# PS2.net
KiCad netlist of a schematic drawn in EAGLE
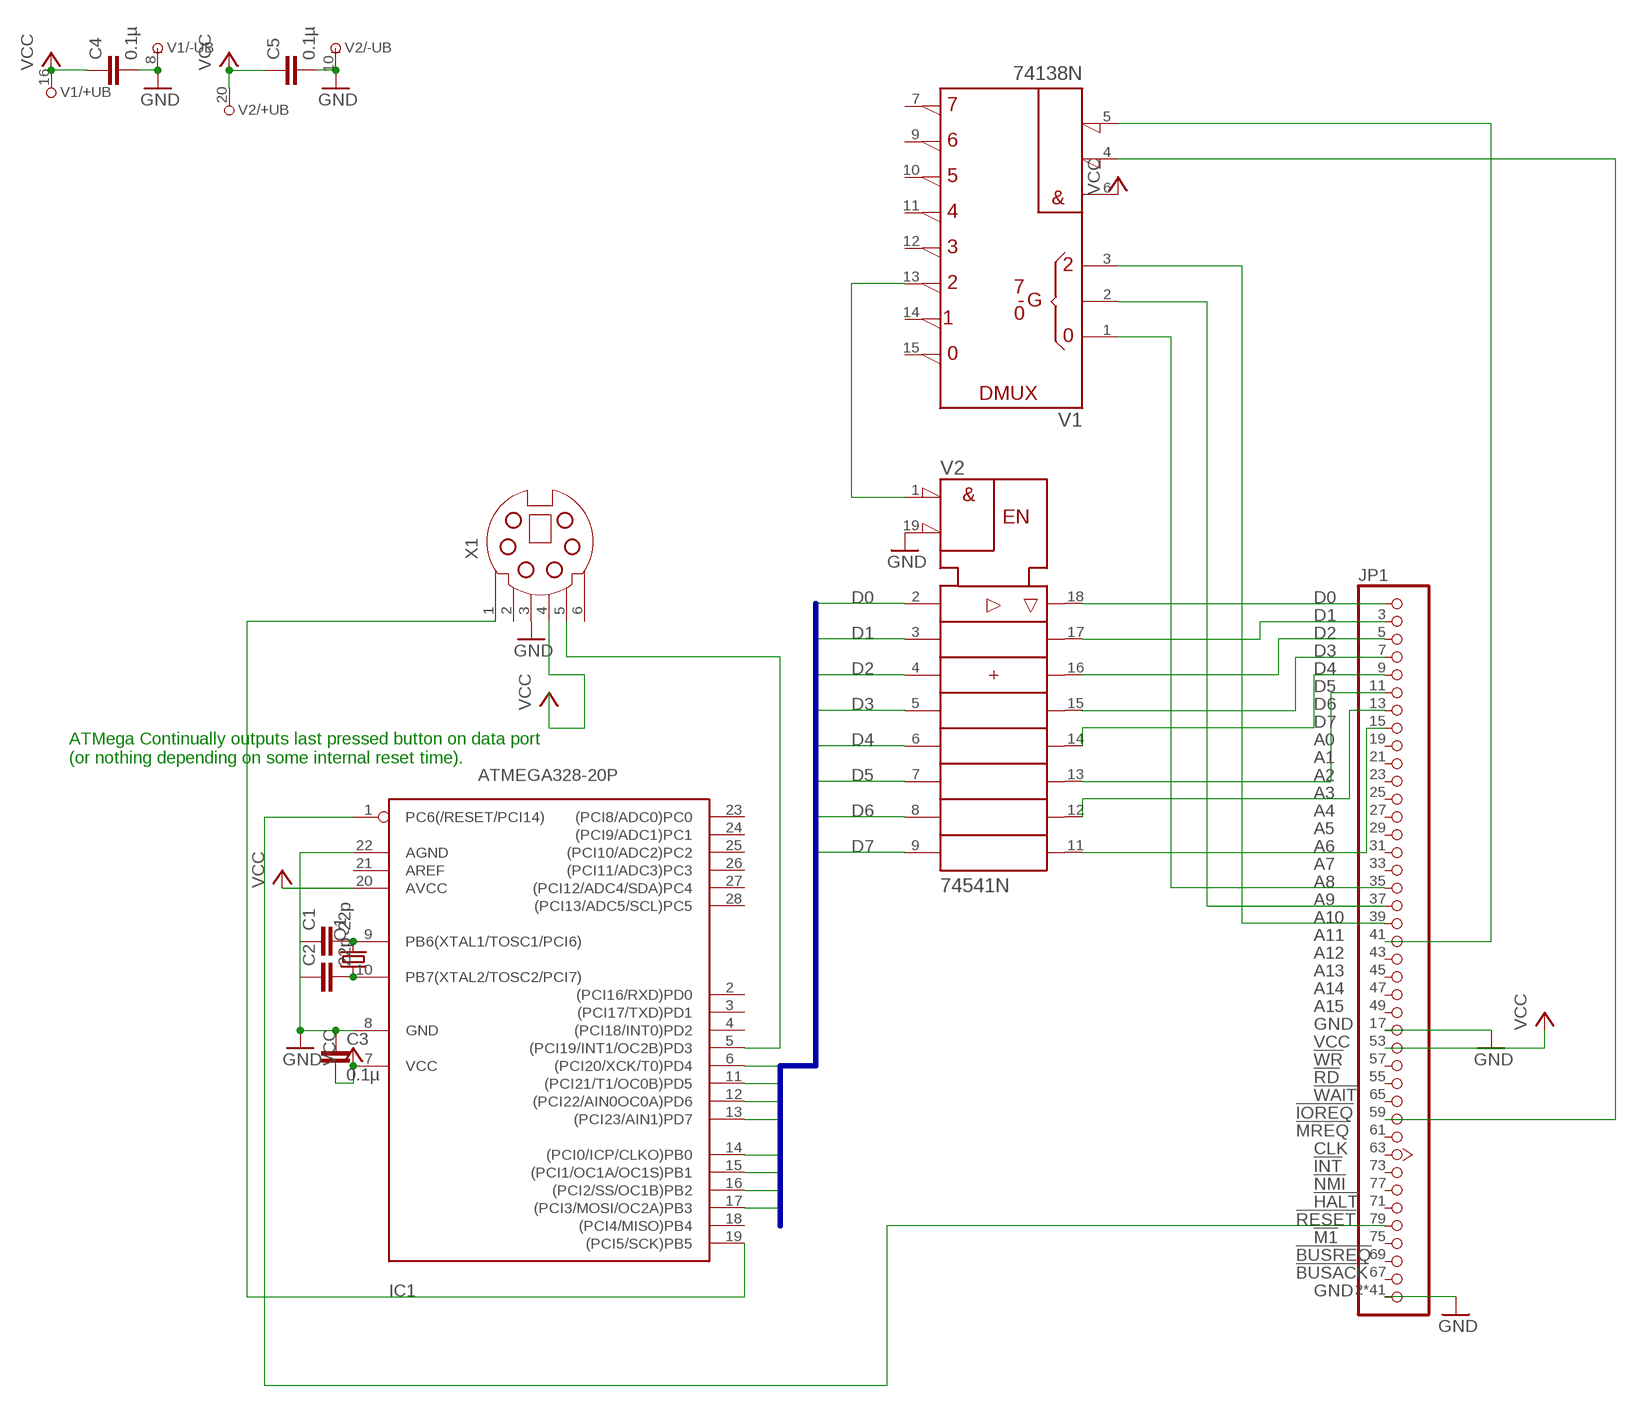
[diagram p0: schematic, sheet 1]

(export (version "E")
  (design (tool "Eeschema 10.0.6"))
  (components
    (comp (ref "C1")
      (value "22p")
      (footprint "eagle-import:C5B3")
      (libsource (lib "eagle-import") (part "C5/3"))
    )
    (comp (ref "C2")
      (value "22p")
      (footprint "eagle-import:C5B3")
      (libsource (lib "eagle-import") (part "C5/3"))
    )
    (comp (ref "C3")
      (value "0.1µ")
      (footprint "eagle-import:C5B3")
      (libsource (lib "eagle-import") (part "C5/3"))
    )
    (comp (ref "C4")
      (value "0.1µ")
      (footprint "eagle-import:C5B3")
      (libsource (lib "eagle-import") (part "C5/3"))
    )
    (comp (ref "C5")
      (value "0.1µ")
      (footprint "eagle-import:C5B3")
      (libsource (lib "eagle-import") (part "C5/3"))
    )
    (comp (ref "IC1")
      (value "ATMEGA328-20P")
      (footprint "eagle-import:DIL28-3")
      (libsource (lib "eagle-import") (part "ATMEGA328P-20"))
    )
    (comp (ref "JP1")
      (value "JEANNECTOR/90")
      (footprint "eagle-import:2X25_90")
      (libsource (lib "eagle-import") (part "JEANNECTOR/90"))
    )
    (comp (ref "Q1")
      (value "CRYSTALHC49S")
      (footprint "eagle-import:HC49_S")
      (libsource (lib "eagle-import") (part "CRYSTALHC49S"))
    )
    (comp (ref "V1")
      (value "74138N")
      (footprint "eagle-import:DIL16")
      (libsource (lib "eagle-import") (part "74138N"))
    )
    (comp (ref "V2")
      (value "74541N")
      (footprint "eagle-import:DIL20")
      (libsource (lib "eagle-import") (part "74541N"))
    )
    (comp (ref "X1")
      (value "MDSSV-F06")
      (footprint "eagle-import:SSV-BC06")
      (libsource (lib "eagle-import") (part "MDSSV-F06"))
    )
  )
  (nets
    (net (code "1") (name "/D0") (class "Default")
      (node (ref "IC1") (pin "6") (pinfunction "(PCI20/XCK/T0)PD4_6") (pintype "bidirectional"))
      (node (ref "V2") (pin "2") (pinfunction "A1_2") (pintype "input"))
    )
    (net (code "2") (name "/D1") (class "Default")
      (node (ref "IC1") (pin "11") (pinfunction "(PCI21/T1/OC0B)PD5_11") (pintype "bidirectional"))
      (node (ref "V2") (pin "3") (pinfunction "A2_3") (pintype "input"))
    )
    (net (code "3") (name "/D2") (class "Default")
      (node (ref "IC1") (pin "12") (pinfunction "(PCI22/AIN0OC0A)PD6_12") (pintype "bidirectional"))
      (node (ref "V2") (pin "4") (pinfunction "A3_4") (pintype "input"))
    )
    (net (code "4") (name "/D3") (class "Default")
      (node (ref "IC1") (pin "13") (pinfunction "(PCI23/AIN1)PD7_13") (pintype "bidirectional"))
      (node (ref "V2") (pin "5") (pinfunction "A4_5") (pintype "input"))
    )
    (net (code "5") (name "/D4") (class "Default")
      (node (ref "IC1") (pin "14") (pinfunction "(PCI0/ICP/CLKO)PB0_14") (pintype "bidirectional"))
      (node (ref "V2") (pin "6") (pinfunction "A5_6") (pintype "input"))
    )
    (net (code "6") (name "/D5") (class "Default")
      (node (ref "IC1") (pin "15") (pinfunction "(PCI1/OC1A/OC1S)PB1_15") (pintype "bidirectional"))
      (node (ref "V2") (pin "7") (pinfunction "A6_7") (pintype "input"))
    )
    (net (code "7") (name "/D6") (class "Default")
      (node (ref "IC1") (pin "16") (pinfunction "(PCI2/SS/OC1B)PB2_16") (pintype "bidirectional"))
      (node (ref "V2") (pin "8") (pinfunction "A7_8") (pintype "input"))
    )
    (net (code "8") (name "/D7") (class "Default")
      (node (ref "IC1") (pin "17") (pinfunction "(PCI3/MOSI/OC2A)PB3_17") (pintype "bidirectional"))
      (node (ref "V2") (pin "9") (pinfunction "A8_9") (pintype "input"))
    )
    (net (code "9") (name "GND") (class "Default")
      (node (ref "C3") (pin "1") (pinfunction "1_1") (pintype "passive"))
      (node (ref "C4") (pin "2") (pinfunction "2_2") (pintype "passive"))
      (node (ref "C5") (pin "2") (pinfunction "2_2") (pintype "passive"))
      (node (ref "IC1") (pin "22") (pinfunction "AGND_22") (pintype "bidirectional"))
      (node (ref "IC1") (pin "8") (pinfunction "GND_8") (pintype "bidirectional"))
      (node (ref "JP1") (pin "10") (pinfunction "GND_10") (pintype "power_in"))
      (node (ref "JP1") (pin "12") (pinfunction "GND_12") (pintype "power_in"))
      (node (ref "JP1") (pin "14") (pinfunction "GND_14") (pintype "power_in"))
      (node (ref "JP1") (pin "16") (pinfunction "GND_16") (pintype "power_in"))
      (node (ref "JP1") (pin "17") (pinfunction "GND_17") (pintype "power_in"))
      (node (ref "JP1") (pin "18") (pinfunction "GND_18") (pintype "power_in"))
      (node (ref "JP1") (pin "2") (pinfunction "GND_2") (pintype "power_in"))
      (node (ref "JP1") (pin "20") (pinfunction "GND_20") (pintype "power_in"))
      (node (ref "JP1") (pin "22") (pinfunction "GND_22") (pintype "power_in"))
      (node (ref "JP1") (pin "24") (pinfunction "GND_24") (pintype "power_in"))
      (node (ref "JP1") (pin "26") (pinfunction "GND_26") (pintype "power_in"))
      (node (ref "JP1") (pin "28") (pinfunction "GND_28") (pintype "power_in"))
      (node (ref "JP1") (pin "30") (pinfunction "GND_30") (pintype "power_in"))
      (node (ref "JP1") (pin "32") (pinfunction "GND_32") (pintype "power_in"))
      (node (ref "JP1") (pin "34") (pinfunction "GND_34") (pintype "power_in"))
      (node (ref "JP1") (pin "36") (pinfunction "GND_36") (pintype "power_in"))
      (node (ref "JP1") (pin "38") (pinfunction "GND_38") (pintype "power_in"))
      (node (ref "JP1") (pin "4") (pinfunction "GND_4") (pintype "power_in"))
      (node (ref "JP1") (pin "40") (pinfunction "GND_40") (pintype "power_in"))
      (node (ref "JP1") (pin "42") (pinfunction "GND_42") (pintype "power_in"))
      (node (ref "JP1") (pin "44") (pinfunction "GND_44") (pintype "power_in"))
      (node (ref "JP1") (pin "46") (pinfunction "GND_46") (pintype "power_in"))
      (node (ref "JP1") (pin "48") (pinfunction "GND_48") (pintype "power_in"))
      (node (ref "JP1") (pin "50") (pinfunction "GND_50") (pintype "power_in"))
      (node (ref "JP1") (pin "51") (pinfunction "GND_51") (pintype "power_in"))
      (node (ref "JP1") (pin "52") (pinfunction "GND_52") (pintype "power_in"))
      (node (ref "JP1") (pin "54") (pinfunction "GND_54") (pintype "power_in"))
      (node (ref "JP1") (pin "56") (pinfunction "GND_56") (pintype "power_in"))
      (node (ref "JP1") (pin "58") (pinfunction "GND_58") (pintype "power_in"))
      (node (ref "JP1") (pin "6") (pinfunction "GND_6") (pintype "power_in"))
      (node (ref "JP1") (pin "60") (pinfunction "GND_60") (pintype "power_in"))
      (node (ref "JP1") (pin "62") (pinfunction "GND_62") (pintype "power_in"))
      (node (ref "JP1") (pin "64") (pinfunction "GND_64") (pintype "power_in"))
      (node (ref "JP1") (pin "66") (pinfunction "GND_66") (pintype "power_in"))
      (node (ref "JP1") (pin "68") (pinfunction "GND_68") (pintype "power_in"))
      (node (ref "JP1") (pin "70") (pinfunction "GND_70") (pintype "power_in"))
      (node (ref "JP1") (pin "72") (pinfunction "GND_72") (pintype "power_in"))
      (node (ref "JP1") (pin "74") (pinfunction "GND_74") (pintype "power_in"))
      (node (ref "JP1") (pin "76") (pinfunction "GND_76") (pintype "power_in"))
      (node (ref "JP1") (pin "78") (pinfunction "GND_78") (pintype "power_in"))
      (node (ref "JP1") (pin "8") (pinfunction "GND_8") (pintype "power_in"))
      (node (ref "JP1") (pin "80") (pinfunction "GND_80") (pintype "power_in"))
      (node (ref "V1") (pin "8") (pinfunction "-UB_8") (pintype "power_in"))
      (node (ref "V2") (pin "10") (pinfunction "-UB_10") (pintype "power_in"))
      (node (ref "V2") (pin "19") (pinfunction "~{G2}_19") (pintype "input"))
      (node (ref "X1") (pin "3") (pinfunction "3_3") (pintype "passive"))
    )
    (net (code "10") (name "Net-(IC1-(PCI5{slash}SCK)PB5)") (class "Default")
      (node (ref "IC1") (pin "19") (pinfunction "(PCI5/SCK)PB5_19") (pintype "bidirectional"))
      (node (ref "X1") (pin "1") (pinfunction "1_1") (pintype "passive"))
    )
    (net (code "11") (name "Net-(IC1-(PCI19{slash}INT1{slash}OC2B)PD3)") (class "Default")
      (node (ref "IC1") (pin "5") (pinfunction "(PCI19/INT1/OC2B)PD3_5") (pintype "bidirectional"))
      (node (ref "X1") (pin "5") (pinfunction "5_5") (pintype "passive"))
    )
    (net (code "12") (name "Net-(IC1-PB6(XTAL1{slash}TOSC1{slash}PCI6))") (class "Default")
      (node (ref "C1") (pin "2") (pinfunction "2_2") (pintype "passive"))
      (node (ref "IC1") (pin "9") (pinfunction "PB6(XTAL1/TOSC1/PCI6)_9") (pintype "bidirectional"))
      (node (ref "Q1") (pin "2") (pinfunction "2_2") (pintype "passive"))
    )
    (net (code "13") (name "Net-(IC1-PB7(XTAL2{slash}TOSC2{slash}PCI7))") (class "Default")
      (node (ref "C2") (pin "2") (pinfunction "2_2") (pintype "passive"))
      (node (ref "IC1") (pin "10") (pinfunction "PB7(XTAL2/TOSC2/PCI7)_10") (pintype "bidirectional"))
      (node (ref "Q1") (pin "1") (pinfunction "1_1") (pintype "passive"))
    )
    (net (code "14") (name "Net-(IC1-PC6({slash}RESET{slash}PCI14))") (class "Default")
      (node (ref "IC1") (pin "1") (pinfunction "PC6(/RESET/PCI14)_1") (pintype "bidirectional"))
      (node (ref "JP1") (pin "79") (pinfunction "~{RESET}_79") (pintype "bidirectional"))
    )
    (net (code "15") (name "Net-(JP1-A8)") (class "Default")
      (node (ref "JP1") (pin "35") (pinfunction "A8_35") (pintype "bidirectional"))
      (node (ref "V1") (pin "1") (pinfunction "A_1") (pintype "input"))
    )
    (net (code "16") (name "Net-(JP1-A9)") (class "Default")
      (node (ref "JP1") (pin "37") (pinfunction "A9_37") (pintype "bidirectional"))
      (node (ref "V1") (pin "2") (pinfunction "B_2") (pintype "input"))
    )
    (net (code "17") (name "Net-(JP1-A10)") (class "Default")
      (node (ref "JP1") (pin "39") (pinfunction "A10_39") (pintype "bidirectional"))
      (node (ref "V1") (pin "3") (pinfunction "C_3") (pintype "input"))
    )
    (net (code "18") (name "Net-(JP1-A11)") (class "Default")
      (node (ref "JP1") (pin "41") (pinfunction "A11_41") (pintype "bidirectional"))
      (node (ref "V1") (pin "5") (pinfunction "~{G2B}_5") (pintype "input"))
    )
    (net (code "19") (name "Net-(JP1-D0)") (class "Default")
      (node (ref "JP1") (pin "1") (pinfunction "D0_1") (pintype "bidirectional"))
      (node (ref "V2") (pin "18") (pinfunction "Y1_18") (pintype "tri_state"))
    )
    (net (code "20") (name "Net-(JP1-D1)") (class "Default")
      (node (ref "JP1") (pin "3") (pinfunction "D1_3") (pintype "bidirectional"))
      (node (ref "V2") (pin "17") (pinfunction "Y2_17") (pintype "tri_state"))
    )
    (net (code "21") (name "Net-(JP1-D2)") (class "Default")
      (node (ref "JP1") (pin "5") (pinfunction "D2_5") (pintype "bidirectional"))
      (node (ref "V2") (pin "16") (pinfunction "Y3_16") (pintype "tri_state"))
    )
    (net (code "22") (name "Net-(JP1-D3)") (class "Default")
      (node (ref "JP1") (pin "7") (pinfunction "D3_7") (pintype "bidirectional"))
      (node (ref "V2") (pin "15") (pinfunction "Y4_15") (pintype "tri_state"))
    )
    (net (code "23") (name "Net-(JP1-D4)") (class "Default")
      (node (ref "JP1") (pin "9") (pinfunction "D4_9") (pintype "bidirectional"))
      (node (ref "V2") (pin "14") (pinfunction "Y5_14") (pintype "tri_state"))
    )
    (net (code "24") (name "Net-(JP1-D5)") (class "Default")
      (node (ref "JP1") (pin "11") (pinfunction "D5_11") (pintype "bidirectional"))
      (node (ref "V2") (pin "13") (pinfunction "Y6_13") (pintype "tri_state"))
    )
    (net (code "25") (name "Net-(JP1-D6)") (class "Default")
      (node (ref "JP1") (pin "13") (pinfunction "D6_13") (pintype "bidirectional"))
      (node (ref "V2") (pin "12") (pinfunction "Y7_12") (pintype "tri_state"))
    )
    (net (code "26") (name "Net-(JP1-D7)") (class "Default")
      (node (ref "JP1") (pin "15") (pinfunction "D7_15") (pintype "bidirectional"))
      (node (ref "V2") (pin "11") (pinfunction "Y8_11") (pintype "tri_state"))
    )
    (net (code "27") (name "Net-(JP1-~{IOREQ})") (class "Default")
      (node (ref "JP1") (pin "59") (pinfunction "~{IOREQ}_59") (pintype "output"))
      (node (ref "V1") (pin "4") (pinfunction "~{G2A}_4") (pintype "input"))
    )
    (net (code "28") (name "Net-(V1C-Y2)") (class "Default")
      (node (ref "V1") (pin "13") (pinfunction "Y2_13") (pintype "output"))
      (node (ref "V2") (pin "1") (pinfunction "~{G1}_1") (pintype "input"))
    )
    (net (code "29") (name "VCC") (class "Default")
      (node (ref "C3") (pin "2") (pinfunction "2_2") (pintype "passive"))
      (node (ref "C4") (pin "1") (pinfunction "1_1") (pintype "passive"))
      (node (ref "C5") (pin "1") (pinfunction "1_1") (pintype "passive"))
      (node (ref "IC1") (pin "20") (pinfunction "AVCC_20") (pintype "bidirectional"))
      (node (ref "IC1") (pin "7") (pinfunction "VCC_7") (pintype "bidirectional"))
      (node (ref "JP1") (pin "53") (pinfunction "VCC_53") (pintype "power_in"))
      (node (ref "V1") (pin "16") (pinfunction "+UB_16") (pintype "power_in"))
      (node (ref "V1") (pin "6") (pinfunction "G1_6") (pintype "input"))
      (node (ref "V2") (pin "20") (pinfunction "+UB_20") (pintype "power_in"))
      (node (ref "X1") (pin "4") (pinfunction "4_4") (pintype "passive"))
    )
    (net (code "30") (name "unconnected-(C1-Pad1)") (class "Default")
      (node (ref "C1") (pin "1") (pinfunction "1_1") (pintype "passive"))
    )
    (net (code "31") (name "unconnected-(C2-Pad1)") (class "Default")
      (node (ref "C2") (pin "1") (pinfunction "1_1") (pintype "passive"))
    )
    (net (code "32") (name "unconnected-(IC1-(PCI4{slash}MISO)PB4-Pad18)") (class "Default")
      (node (ref "IC1") (pin "18") (pinfunction "(PCI4/MISO)PB4_18") (pintype "bidirectional"))
    )
    (net (code "33") (name "unconnected-(IC1-(PCI8{slash}ADC0)PC0-Pad23)") (class "Default")
      (node (ref "IC1") (pin "23") (pinfunction "(PCI8/ADC0)PC0_23") (pintype "bidirectional"))
    )
    (net (code "34") (name "unconnected-(IC1-(PCI9{slash}ADC1)PC1-Pad24)") (class "Default")
      (node (ref "IC1") (pin "24") (pinfunction "(PCI9/ADC1)PC1_24") (pintype "bidirectional"))
    )
    (net (code "35") (name "unconnected-(IC1-(PCI10{slash}ADC2)PC2-Pad25)") (class "Default")
      (node (ref "IC1") (pin "25") (pinfunction "(PCI10/ADC2)PC2_25") (pintype "bidirectional"))
    )
    (net (code "36") (name "unconnected-(IC1-(PCI11{slash}ADC3)PC3-Pad26)") (class "Default")
      (node (ref "IC1") (pin "26") (pinfunction "(PCI11/ADC3)PC3_26") (pintype "bidirectional"))
    )
    (net (code "37") (name "unconnected-(IC1-(PCI12{slash}ADC4{slash}SDA)PC4-Pad27)") (class "Default")
      (node (ref "IC1") (pin "27") (pinfunction "(PCI12/ADC4/SDA)PC4_27") (pintype "bidirectional"))
    )
    (net (code "38") (name "unconnected-(IC1-(PCI13{slash}ADC5{slash}SCL)PC5-Pad28)") (class "Default")
      (node (ref "IC1") (pin "28") (pinfunction "(PCI13/ADC5/SCL)PC5_28") (pintype "bidirectional"))
    )
    (net (code "39") (name "unconnected-(IC1-(PCI16{slash}RXD)PD0-Pad2)") (class "Default")
      (node (ref "IC1") (pin "2") (pinfunction "(PCI16/RXD)PD0_2") (pintype "bidirectional"))
    )
    (net (code "40") (name "unconnected-(IC1-(PCI17{slash}TXD)PD1-Pad3)") (class "Default")
      (node (ref "IC1") (pin "3") (pinfunction "(PCI17/TXD)PD1_3") (pintype "bidirectional"))
    )
    (net (code "41") (name "unconnected-(IC1-(PCI18{slash}INT0)PD2-Pad4)") (class "Default")
      (node (ref "IC1") (pin "4") (pinfunction "(PCI18/INT0)PD2_4") (pintype "bidirectional"))
    )
    (net (code "42") (name "unconnected-(IC1-AREF-Pad21)") (class "Default")
      (node (ref "IC1") (pin "21") (pinfunction "AREF_21") (pintype "bidirectional"))
    )
    (net (code "43") (name "unconnected-(JP1-A0-Pad19)") (class "Default")
      (node (ref "JP1") (pin "19") (pinfunction "A0_19") (pintype "bidirectional"))
    )
    (net (code "44") (name "unconnected-(JP1-A1-Pad21)") (class "Default")
      (node (ref "JP1") (pin "21") (pinfunction "A1_21") (pintype "bidirectional"))
    )
    (net (code "45") (name "unconnected-(JP1-A2-Pad23)") (class "Default")
      (node (ref "JP1") (pin "23") (pinfunction "A2_23") (pintype "bidirectional"))
    )
    (net (code "46") (name "unconnected-(JP1-A3-Pad25)") (class "Default")
      (node (ref "JP1") (pin "25") (pinfunction "A3_25") (pintype "bidirectional"))
    )
    (net (code "47") (name "unconnected-(JP1-A4-Pad27)") (class "Default")
      (node (ref "JP1") (pin "27") (pinfunction "A4_27") (pintype "bidirectional"))
    )
    (net (code "48") (name "unconnected-(JP1-A5-Pad29)") (class "Default")
      (node (ref "JP1") (pin "29") (pinfunction "A5_29") (pintype "bidirectional"))
    )
    (net (code "49") (name "unconnected-(JP1-A6-Pad31)") (class "Default")
      (node (ref "JP1") (pin "31") (pinfunction "A6_31") (pintype "bidirectional"))
    )
    (net (code "50") (name "unconnected-(JP1-A7-Pad33)") (class "Default")
      (node (ref "JP1") (pin "33") (pinfunction "A7_33") (pintype "bidirectional"))
    )
    (net (code "51") (name "unconnected-(JP1-A12-Pad43)") (class "Default")
      (node (ref "JP1") (pin "43") (pinfunction "A12_43") (pintype "bidirectional"))
    )
    (net (code "52") (name "unconnected-(JP1-A13-Pad45)") (class "Default")
      (node (ref "JP1") (pin "45") (pinfunction "A13_45") (pintype "bidirectional"))
    )
    (net (code "53") (name "unconnected-(JP1-A14-Pad47)") (class "Default")
      (node (ref "JP1") (pin "47") (pinfunction "A14_47") (pintype "bidirectional"))
    )
    (net (code "54") (name "unconnected-(JP1-A15-Pad49)") (class "Default")
      (node (ref "JP1") (pin "49") (pinfunction "A15_49") (pintype "bidirectional"))
    )
    (net (code "55") (name "unconnected-(JP1-CLK-Pad63)") (class "Default")
      (node (ref "JP1") (pin "63") (pinfunction "CLK_63") (pintype "passive"))
    )
    (net (code "56") (name "unconnected-(JP1-~{BUSACK}-Pad67)") (class "Default")
      (node (ref "JP1") (pin "67") (pinfunction "~{BUSACK}_67") (pintype "input"))
    )
    (net (code "57") (name "unconnected-(JP1-~{BUSRQ}-Pad69)") (class "Default")
      (node (ref "JP1") (pin "69") (pinfunction "~{BUSRQ}_69") (pintype "output"))
    )
    (net (code "58") (name "unconnected-(JP1-~{HALT}-Pad71)") (class "Default")
      (node (ref "JP1") (pin "71") (pinfunction "~{HALT}_71") (pintype "input"))
    )
    (net (code "59") (name "unconnected-(JP1-~{INT}-Pad73)") (class "Default")
      (node (ref "JP1") (pin "73") (pinfunction "~{INT}_73") (pintype "bidirectional"))
    )
    (net (code "60") (name "unconnected-(JP1-~{M1}-Pad75)") (class "Default")
      (node (ref "JP1") (pin "75") (pinfunction "~{M1}_75") (pintype "bidirectional"))
    )
    (net (code "61") (name "unconnected-(JP1-~{MREQ}-Pad61)") (class "Default")
      (node (ref "JP1") (pin "61") (pinfunction "~{MREQ}_61") (pintype "output"))
    )
    (net (code "62") (name "unconnected-(JP1-~{NMI}-Pad77)") (class "Default")
      (node (ref "JP1") (pin "77") (pinfunction "~{NMI}_77") (pintype "bidirectional"))
    )
    (net (code "63") (name "unconnected-(JP1-~{RD}-Pad55)") (class "Default")
      (node (ref "JP1") (pin "55") (pinfunction "~{RD}_55") (pintype "output"))
    )
    (net (code "64") (name "unconnected-(JP1-~{WAIT}-Pad65)") (class "Default")
      (node (ref "JP1") (pin "65") (pinfunction "~{WAIT}_65") (pintype "input"))
    )
    (net (code "65") (name "unconnected-(JP1-~{WR}-Pad57)") (class "Default")
      (node (ref "JP1") (pin "57") (pinfunction "~{WR}_57") (pintype "output"))
    )
    (net (code "66") (name "unconnected-(V1C-Y0-Pad15)") (class "Default")
      (node (ref "V1") (pin "15") (pinfunction "Y0_15") (pintype "output"))
    )
    (net (code "67") (name "unconnected-(V1C-Y1-Pad14)") (class "Default")
      (node (ref "V1") (pin "14") (pinfunction "Y1_14") (pintype "output"))
    )
    (net (code "68") (name "unconnected-(V1C-Y3-Pad12)") (class "Default")
      (node (ref "V1") (pin "12") (pinfunction "Y3_12") (pintype "output"))
    )
    (net (code "69") (name "unconnected-(V1C-Y4-Pad11)") (class "Default")
      (node (ref "V1") (pin "11") (pinfunction "Y4_11") (pintype "output"))
    )
    (net (code "70") (name "unconnected-(V1C-Y5-Pad10)") (class "Default")
      (node (ref "V1") (pin "10") (pinfunction "Y5_10") (pintype "output"))
    )
    (net (code "71") (name "unconnected-(V1C-Y6-Pad9)") (class "Default")
      (node (ref "V1") (pin "9") (pinfunction "Y6_9") (pintype "output"))
    )
    (net (code "72") (name "unconnected-(V1C-Y7-Pad7)") (class "Default")
      (node (ref "V1") (pin "7") (pinfunction "Y7_7") (pintype "output"))
    )
    (net (code "73") (name "unconnected-(X1-Pad2)") (class "Default")
      (node (ref "X1") (pin "2") (pinfunction "2_2") (pintype "passive"))
    )
    (net (code "74") (name "unconnected-(X1-Pad6)") (class "Default")
      (node (ref "X1") (pin "6") (pinfunction "6_6") (pintype "passive"))
    )
  )
)
